# HominiPulseSensorBatt.net
KiCad netlist of a schematic drawn in EAGLE
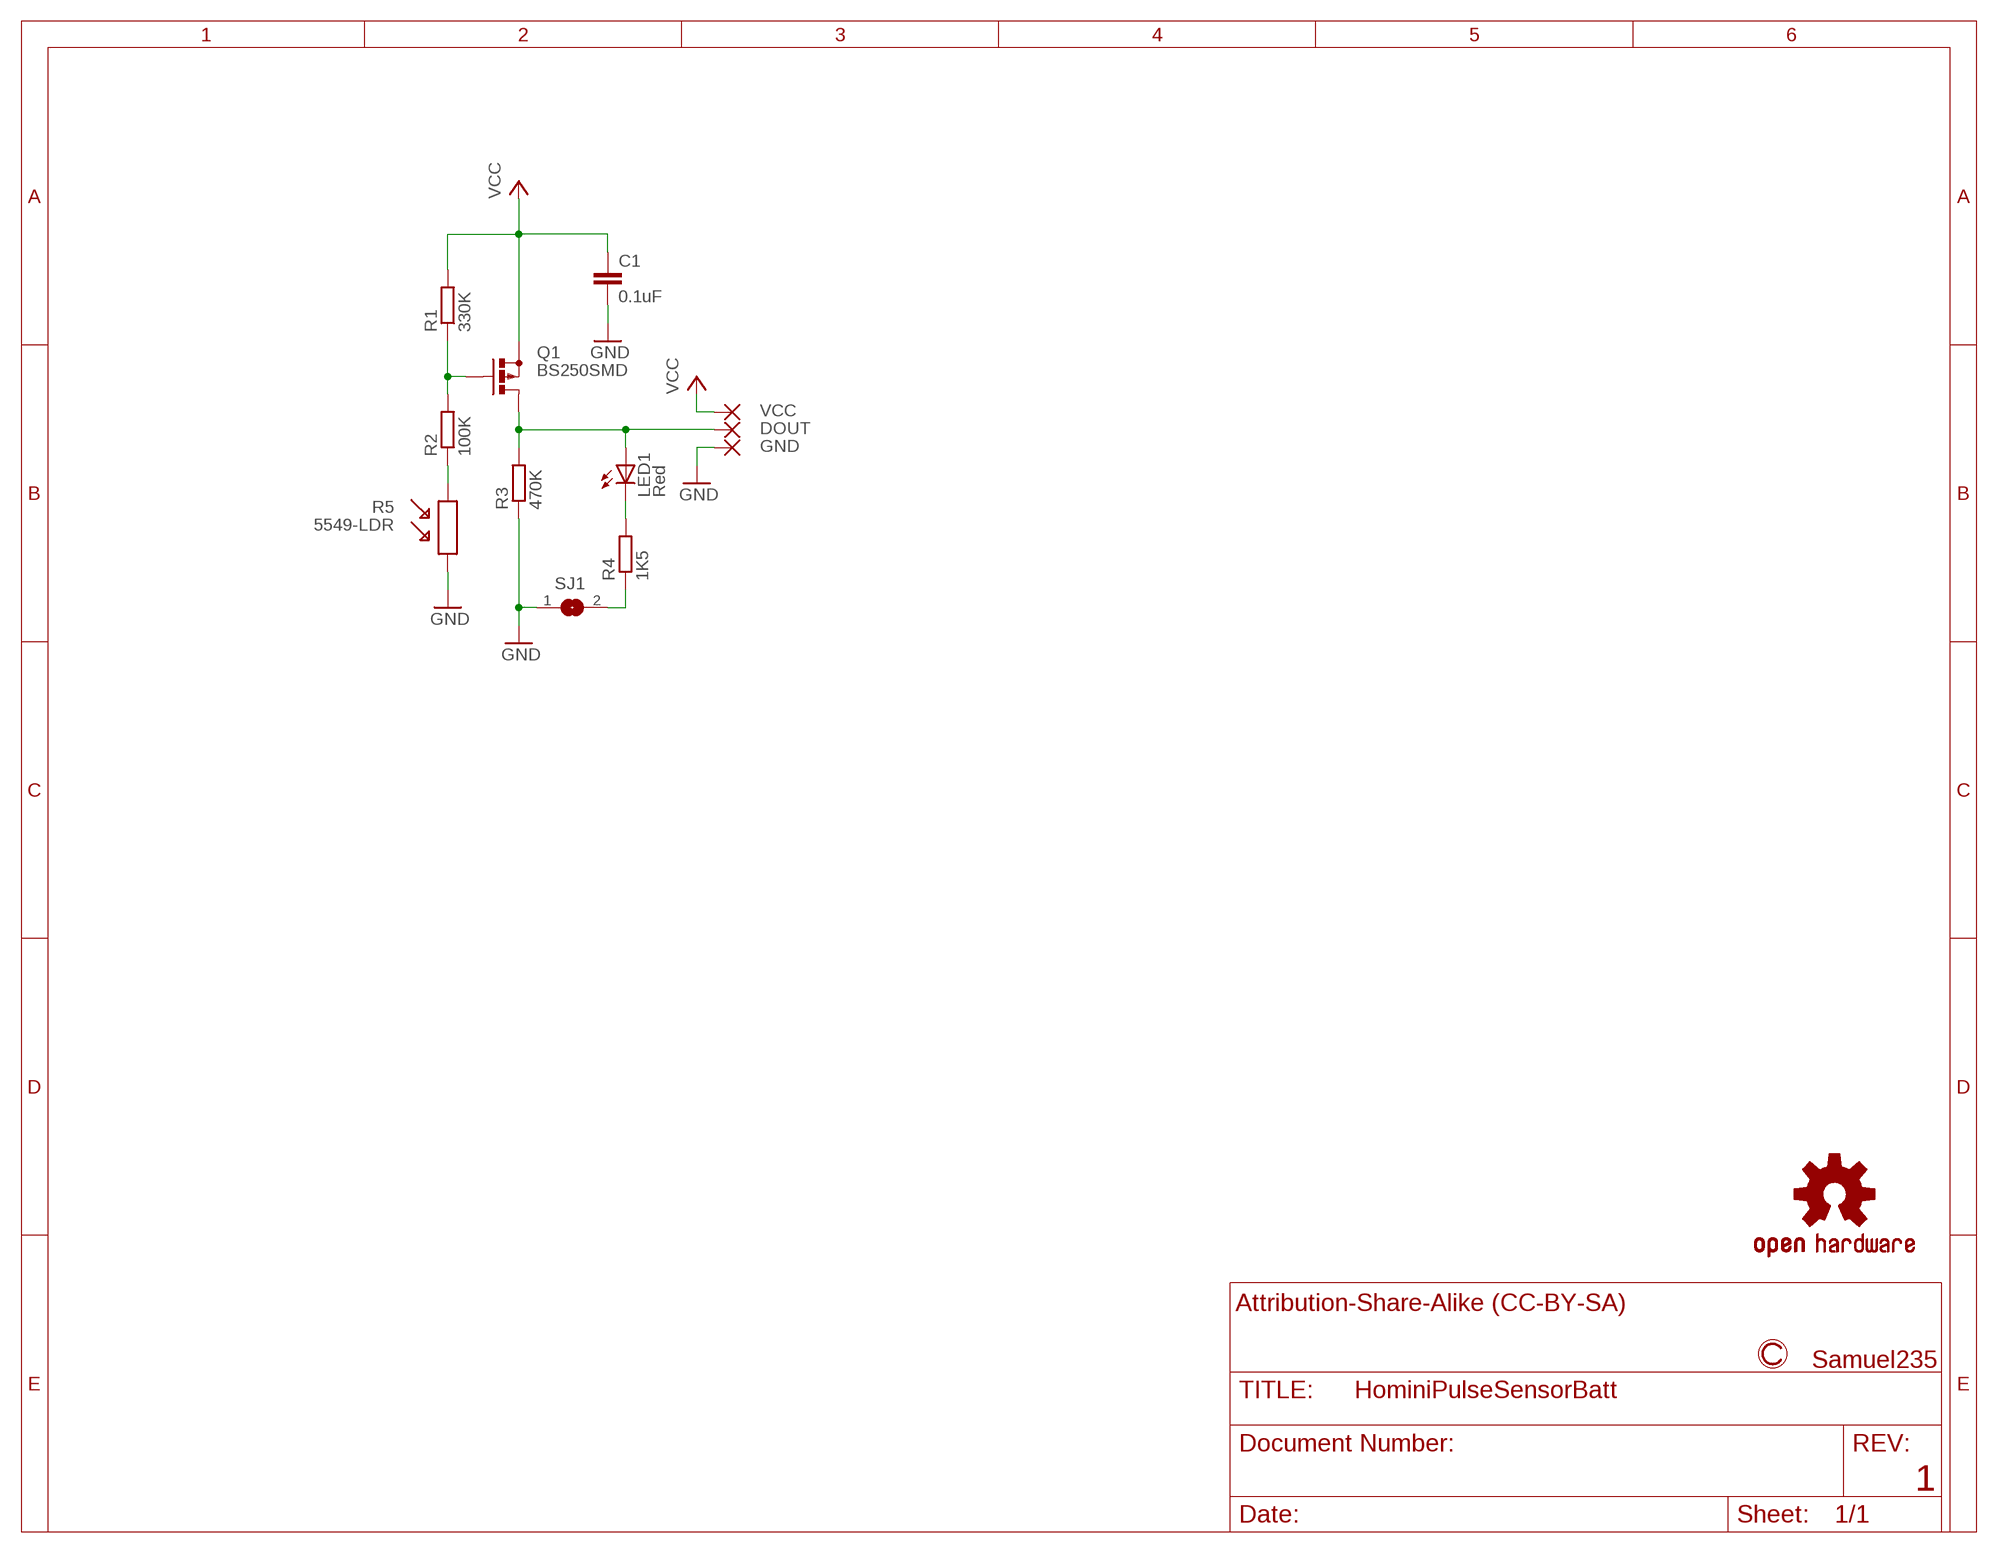
[diagram p0: schematic, sheet 1]

(export (version "E")
  (design (tool "Eeschema 10.0.6"))
  (components
    (comp (ref "C1")
      (value "0.1uF")
      (footprint "eagle-import:C0603")
      (libsource (lib "eagle-import") (part "C-EUC0603"))
    )
    (comp (ref "DOUT")
      (value "SMD2")
      (footprint "eagle-import:SMD1,27-2,54")
      (libsource (lib "eagle-import") (part "SMD2"))
    )
    (comp (ref "GND")
      (value "SMD2")
      (footprint "eagle-import:SMD1,27-2,54")
      (libsource (lib "eagle-import") (part "SMD2"))
    )
    (comp (ref "LED1")
      (value "Red")
      (footprint "eagle-import:LED3MM")
      (libsource (lib "eagle-import") (part "LED3MM"))
    )
    (comp (ref "LOGO1")
      (value "OSHW-LOGOS")
      (footprint "eagle-import:OSHW-LOGO-S")
      (libsource (lib "eagle-import") (part "OSHW-LOGOS"))
    )
    (comp (ref "Q1")
      (value "BS250SMD")
      (footprint "eagle-import:SOT23")
      (libsource (lib "eagle-import") (part "BS250SMD"))
    )
    (comp (ref "R1")
      (value "330K")
      (footprint "eagle-import:R0603")
      (libsource (lib "eagle-import") (part "R-EU_R0603"))
    )
    (comp (ref "R2")
      (value "100K")
      (footprint "eagle-import:R0603")
      (libsource (lib "eagle-import") (part "R-EU_R0603"))
    )
    (comp (ref "R3")
      (value "470K")
      (footprint "eagle-import:R0603")
      (libsource (lib "eagle-import") (part "R-EU_R0603"))
    )
    (comp (ref "R4")
      (value "1K5")
      (footprint "eagle-import:R0603")
      (libsource (lib "eagle-import") (part "R-EU_R0603"))
    )
    (comp (ref "R5")
      (value "5549-LDR")
      (footprint "eagle-import:LDR-PTH")
      (libsource (lib "eagle-import") (part "5549-LDR"))
    )
    (comp (ref "SJ1") (value "SJ") (footprint "eagle-import:SJ") (libsource (lib "eagle-import") (part "SJ")))
    (comp (ref "VCC")
      (value "SMD2")
      (footprint "eagle-import:SMD1,27-2,54")
      (libsource (lib "eagle-import") (part "SMD2"))
    )
  )
  (nets
    (net (code "1") (name "GND") (class "Default")
      (node (ref "C1") (pin "2") (pinfunction "2_2") (pintype "passive"))
      (node (ref "GND") (pin "1") (pinfunction "P_1") (pintype "passive"))
      (node (ref "R3") (pin "1") (pinfunction "1_1") (pintype "passive"))
      (node (ref "R5") (pin "1") (pinfunction "P$1_1") (pintype "bidirectional"))
      (node (ref "SJ1") (pin "1") (pinfunction "1_1") (pintype "passive"))
    )
    (net (code "2") (name "Net-(DOUT-P)") (class "Default")
      (node (ref "DOUT") (pin "1") (pinfunction "P_1") (pintype "passive"))
      (node (ref "LED1") (pin "A") (pinfunction "A_A") (pintype "passive"))
      (node (ref "Q1") (pin "3") (pinfunction "D_3") (pintype "passive"))
      (node (ref "R3") (pin "2") (pinfunction "2_2") (pintype "passive"))
    )
    (net (code "3") (name "Net-(LED1-C)") (class "Default")
      (node (ref "LED1") (pin "K") (pinfunction "C_K") (pintype "passive"))
      (node (ref "R4") (pin "2") (pinfunction "2_2") (pintype "passive"))
    )
    (net (code "4") (name "Net-(Q1-G)") (class "Default")
      (node (ref "Q1") (pin "1") (pinfunction "G_1") (pintype "passive"))
      (node (ref "R1") (pin "1") (pinfunction "1_1") (pintype "passive"))
      (node (ref "R2") (pin "2") (pinfunction "2_2") (pintype "passive"))
    )
    (net (code "5") (name "Net-(R4-Pad1)") (class "Default")
      (node (ref "R4") (pin "1") (pinfunction "1_1") (pintype "passive"))
      (node (ref "SJ1") (pin "2") (pinfunction "2_2") (pintype "passive"))
    )
    (net (code "6") (name "Net-(R5-P$2)") (class "Default")
      (node (ref "R2") (pin "1") (pinfunction "1_1") (pintype "passive"))
      (node (ref "R5") (pin "2") (pinfunction "P$2_2") (pintype "bidirectional"))
    )
    (net (code "7") (name "VCC") (class "Default")
      (node (ref "C1") (pin "1") (pinfunction "1_1") (pintype "passive"))
      (node (ref "Q1") (pin "2") (pinfunction "S_2") (pintype "passive"))
      (node (ref "R1") (pin "2") (pinfunction "2_2") (pintype "passive"))
      (node (ref "VCC") (pin "1") (pinfunction "P_1") (pintype "passive"))
    )
  )
)
